# ATtiny85_programmer_board.net
KiCad netlist of a schematic drawn in EAGLE
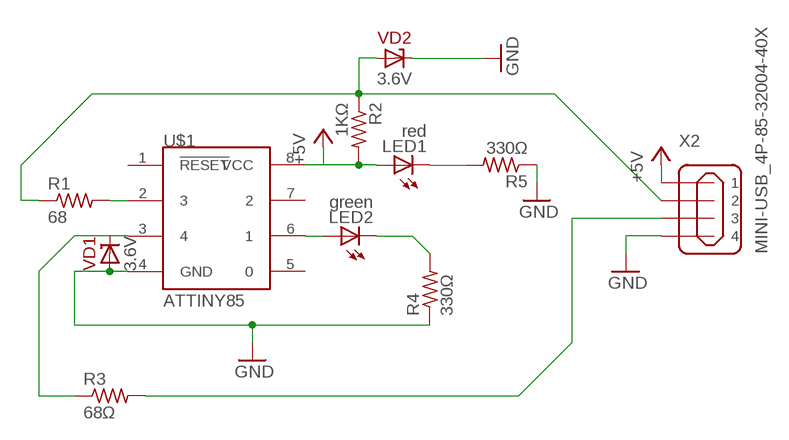
[diagram p0: schematic, sheet 1]

(export (version "E")
  (design (tool "Eeschema 10.0.6"))
  (components
    (comp (ref "LED1")
      (value "red")
      (footprint "eagle-import:LED3MM")
      (libsource (lib "eagle-import") (part "LED3MM"))
    )
    (comp (ref "LED2")
      (value "green")
      (footprint "eagle-import:LED3MM")
      (libsource (lib "eagle-import") (part "LED3MM"))
    )
    (comp (ref "R1")
      (value "68")
      (footprint "eagle-import:0204V")
      (libsource (lib "eagle-import") (part "R-US_0204/2V"))
    )
    (comp (ref "R2")
      (value "1KΩ")
      (footprint "eagle-import:0204V")
      (libsource (lib "eagle-import") (part "R-US_0204/2V"))
    )
    (comp (ref "R3")
      (value "68Ω")
      (footprint "eagle-import:0204V")
      (libsource (lib "eagle-import") (part "R-US_0204/2V"))
    )
    (comp (ref "R4")
      (value "330Ω")
      (footprint "eagle-import:0204V")
      (libsource (lib "eagle-import") (part "R-US_0204/2V"))
    )
    (comp (ref "R5")
      (value "330Ω")
      (footprint "eagle-import:0204V")
      (libsource (lib "eagle-import") (part "R-US_0204/2V"))
    )
    (comp (ref "U$1")
      (value "ATTINY85")
      (footprint "eagle-import:8P3")
      (libsource (lib "eagle-import") (part "ATTINY85"))
    )
    (comp (ref "VD1")
      (value "3.6V")
      (footprint "eagle-import:DO35-7")
      (libsource (lib "eagle-import") (part "?5.6V(1N5232)"))
    )
    (comp (ref "VD2")
      (value "3.6V")
      (footprint "eagle-import:DO35-7")
      (libsource (lib "eagle-import") (part "?5.6V(1N5232)"))
    )
    (comp (ref "X2")
      (value "MINI-USB_4P-85-32004-40X")
      (footprint "eagle-import:85-32004-40X")
      (libsource (lib "eagle-import") (part "MINI-USB_4P-85-32004-40X"))
    )
  )
  (nets
    (net (code "1") (name "+5V") (class "Default")
      (node (ref "LED1") (pin "A") (pinfunction "A_A") (pintype "passive"))
      (node (ref "R2") (pin "2") (pinfunction "2_2") (pintype "passive"))
      (node (ref "U$1") (pin "8") (pinfunction "VCC_8") (pintype "power_in"))
      (node (ref "X2") (pin "1") (pinfunction "1_1") (pintype "passive"))
    )
    (net (code "2") (name "GND") (class "Default")
      (node (ref "R4") (pin "1") (pinfunction "1_1") (pintype "passive"))
      (node (ref "R5") (pin "1") (pinfunction "1_1") (pintype "passive"))
      (node (ref "U$1") (pin "4") (pinfunction "GND_4") (pintype "power_in"))
      (node (ref "VD1") (pin "A") (pinfunction "A_A") (pintype "passive"))
      (node (ref "VD2") (pin "C") (pinfunction "C_C") (pintype "passive"))
      (node (ref "X2") (pin "4") (pinfunction "4_4") (pintype "passive"))
    )
    (net (code "3") (name "Net-(LED1-C)") (class "Default")
      (node (ref "LED1") (pin "K") (pinfunction "C_K") (pintype "passive"))
      (node (ref "R5") (pin "2") (pinfunction "2_2") (pintype "passive"))
    )
    (net (code "4") (name "Net-(LED2-C)") (class "Default")
      (node (ref "LED2") (pin "K") (pinfunction "C_K") (pintype "passive"))
      (node (ref "R4") (pin "2") (pinfunction "2_2") (pintype "passive"))
    )
    (net (code "5") (name "Net-(R1-Pad1)") (class "Default")
      (node (ref "R1") (pin "1") (pinfunction "1_1") (pintype "passive"))
      (node (ref "R2") (pin "1") (pinfunction "1_1") (pintype "passive"))
      (node (ref "VD2") (pin "A") (pinfunction "A_A") (pintype "passive"))
      (node (ref "X2") (pin "2") (pinfunction "2_2") (pintype "passive"))
    )
    (net (code "6") (name "Net-(R3-Pad2)") (class "Default")
      (node (ref "R3") (pin "2") (pinfunction "2_2") (pintype "passive"))
      (node (ref "X2") (pin "3") (pinfunction "3_3") (pintype "passive"))
    )
    (net (code "7") (name "Net-(U$1-1)") (class "Default")
      (node (ref "LED2") (pin "A") (pinfunction "A_A") (pintype "passive"))
      (node (ref "U$1") (pin "6") (pinfunction "1_6") (pintype "bidirectional"))
    )
    (net (code "8") (name "Net-(U$1-3)") (class "Default")
      (node (ref "R1") (pin "2") (pinfunction "2_2") (pintype "passive"))
      (node (ref "U$1") (pin "2") (pinfunction "3_2") (pintype "bidirectional"))
    )
    (net (code "9") (name "Net-(U$1-4)") (class "Default")
      (node (ref "R3") (pin "1") (pinfunction "1_1") (pintype "passive"))
      (node (ref "U$1") (pin "3") (pinfunction "4_3") (pintype "bidirectional"))
      (node (ref "VD1") (pin "C") (pinfunction "C_C") (pintype "passive"))
    )
    (net (code "10") (name "unconnected-(U$1-0-Pad5)") (class "Default")
      (node (ref "U$1") (pin "5") (pinfunction "0_5") (pintype "bidirectional"))
    )
    (net (code "11") (name "unconnected-(U$1-2-Pad7)") (class "Default")
      (node (ref "U$1") (pin "7") (pinfunction "2_7") (pintype "bidirectional"))
    )
    (net (code "12") (name "unconnected-(U$1-~{RESET}-Pad1)") (class "Default")
      (node (ref "U$1") (pin "1") (pinfunction "~{RESET}_1") (pintype "bidirectional"))
    )
  )
)
